# Y904A23-GF-DYGDSCH-V1_0.net
KiCad netlist of a schematic drawn in Altium Designer
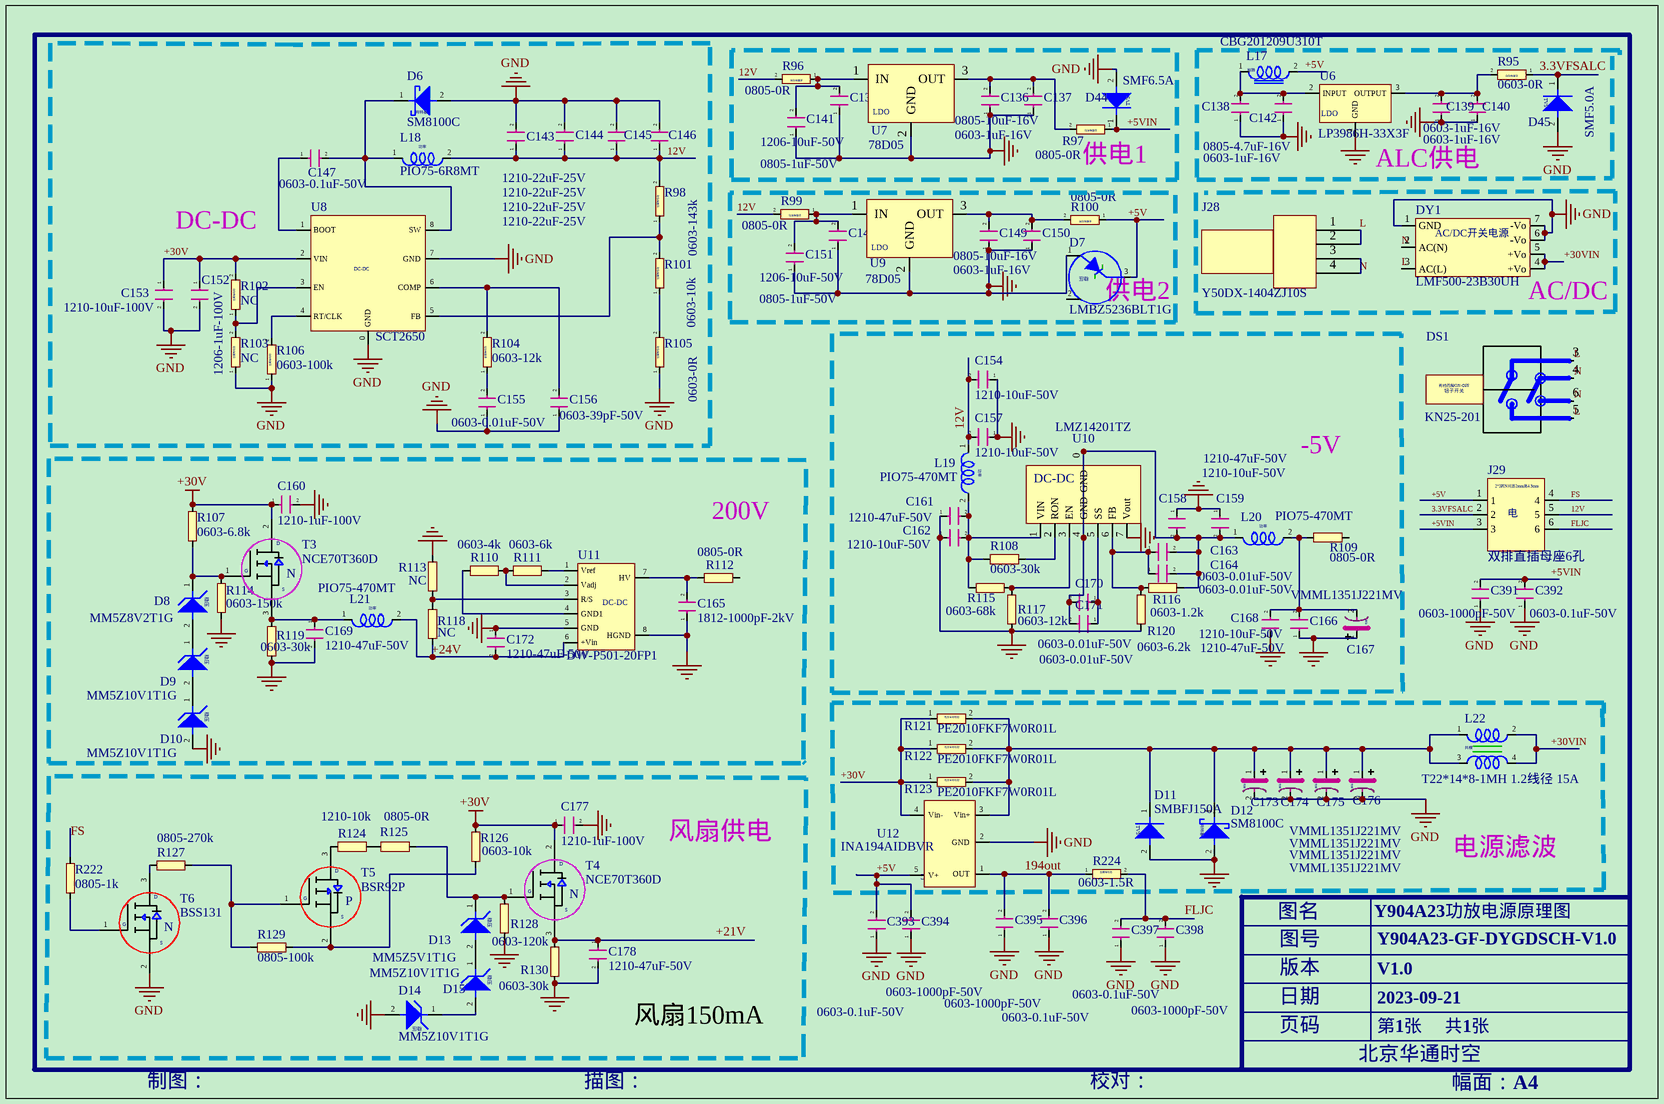
[diagram p0: Y904A23-GF-DYGDSCH-V1.0.SchDoc]

(export (version "E")
  (design (tool "Eeschema 10.0.6"))
  (components
    (comp (ref "C135")
      (value "0805-1uF-50V")
      (footprint "C0805")
      (description "陶瓷电容,厂家")
      (libsource (lib "电容") (part "Cap1"))
    )
    (comp (ref "C136")
      (value "0805-10uF-16V")
      (footprint "C0805")
      (description "陶瓷电容,厂家")
      (libsource (lib "电容") (part "Cap1"))
    )
    (comp (ref "C137")
      (value "0603-1uF-16V")
      (footprint "C0603")
      (description "陶瓷电容,厂家")
      (libsource (lib "电容") (part "Cap1"))
    )
    (comp (ref "C138")
      (value "0805-4.7uF-16V")
      (footprint "C0805")
      (description "陶瓷电容,厂家")
      (libsource (lib "电容") (part "Cap1"))
    )
    (comp (ref "C139")
      (value "0603-1uF-16V")
      (footprint "C0603")
      (description "陶瓷电容,厂家")
      (libsource (lib "电容") (part "Cap1"))
    )
    (comp (ref "C140")
      (value "0603-1uF-16V")
      (footprint "C0603")
      (description "陶瓷电容,厂家")
      (libsource (lib "电容") (part "Cap1"))
    )
    (comp (ref "C141")
      (value "1206-10uF-50V")
      (footprint "C1206")
      (description "陶瓷电容,厂家")
      (libsource (lib "电容") (part "Cap1"))
    )
    (comp (ref "C142")
      (value "0603-1uF-16V")
      (footprint "C0603")
      (description "陶瓷电容,厂家")
      (libsource (lib "电容") (part "Cap1"))
    )
    (comp (ref "C143")
      (value "1210-22uF-25V")
      (footprint "C1210")
      (description "陶瓷电容,厂家")
      (libsource (lib "电容") (part "Cap1"))
    )
    (comp (ref "C144")
      (value "1210-22uF-25V")
      (footprint "C1210")
      (description "陶瓷电容,厂家")
      (libsource (lib "电容") (part "Cap1"))
    )
    (comp (ref "C145")
      (value "1210-22uF-25V")
      (footprint "C1210")
      (description "陶瓷电容,厂家")
      (libsource (lib "电容") (part "Cap1"))
    )
    (comp (ref "C146")
      (value "1210-22uF-25V")
      (footprint "C1210")
      (description "陶瓷电容,厂家")
      (libsource (lib "电容") (part "Cap1"))
    )
    (comp (ref "C147")
      (value "0603-0.1uF-50V")
      (footprint "C0603")
      (description "陶瓷电容,厂家")
      (libsource (lib "电容") (part "Cap1"))
    )
    (comp (ref "C148")
      (value "0805-1uF-50V")
      (footprint "C0805")
      (description "陶瓷电容,厂家")
      (libsource (lib "电容") (part "Cap1"))
    )
    (comp (ref "C149")
      (value "0805-10uF-16V")
      (footprint "C0805")
      (description "陶瓷电容,厂家")
      (libsource (lib "电容") (part "Cap1"))
    )
    (comp (ref "C150")
      (value "0603-1uF-16V")
      (footprint "C0603")
      (description "陶瓷电容,厂家")
      (libsource (lib "电容") (part "Cap1"))
    )
    (comp (ref "C151")
      (value "1206-10uF-50V")
      (footprint "C1206")
      (description "陶瓷电容,厂家")
      (libsource (lib "电容") (part "Cap1"))
    )
    (comp (ref "C152")
      (value "1206-1uF-100V")
      (footprint "C1206")
      (description "陶瓷电容,厂家")
      (libsource (lib "电容") (part "Cap1"))
    )
    (comp (ref "C153")
      (value "1210-10uF-100V")
      (footprint "C1210")
      (description "陶瓷电容,厂家")
      (libsource (lib "电容") (part "Cap1"))
    )
    (comp (ref "C154")
      (value "1210-10uF-50V")
      (footprint "C1210")
      (description "陶瓷电容,厂家")
      (libsource (lib "电容") (part "Cap1"))
    )
    (comp (ref "C155")
      (value "0603-0.01uF-50V")
      (footprint "C0603")
      (description "陶瓷电容,厂家")
      (libsource (lib "电容") (part "Cap1"))
    )
    (comp (ref "C156")
      (value "0603-39pF-50V")
      (footprint "C0603")
      (description "陶瓷电容,厂家")
      (libsource (lib "电容") (part "Cap1"))
    )
    (comp (ref "C157")
      (value "1210-10uF-50V")
      (footprint "C1210")
      (description "陶瓷电容,厂家")
      (libsource (lib "电容") (part "Cap1"))
    )
    (comp (ref "C158")
      (value "1210-10uF-50V")
      (footprint "C1210")
      (description "陶瓷电容,厂家")
      (libsource (lib "电容") (part "Cap1"))
    )
    (comp (ref "C159")
      (value "1210-47uF-50V")
      (footprint "C1210")
      (description "陶瓷电容,厂家")
      (libsource (lib "电容") (part "Cap1"))
    )
    (comp (ref "C160")
      (value "1210-1uF-100V")
      (footprint "C1210")
      (description "陶瓷电容,厂家")
      (libsource (lib "电容") (part "Cap1"))
    )
    (comp (ref "C161")
      (value "1210-47uF-50V")
      (footprint "C1210")
      (description "陶瓷电容,厂家")
      (libsource (lib "电容") (part "Cap1"))
    )
    (comp (ref "C162")
      (value "1210-10uF-50V")
      (footprint "C1210")
      (description "陶瓷电容,厂家")
      (libsource (lib "电容") (part "Cap1"))
    )
    (comp (ref "C163")
      (value "0603-0.01uF-50V")
      (footprint "C0603")
      (description "陶瓷电容,厂家")
      (libsource (lib "电容") (part "Cap1"))
    )
    (comp (ref "C164")
      (value "0603-0.01uF-50V")
      (footprint "C0603")
      (description "陶瓷电容,厂家")
      (libsource (lib "电容") (part "Cap1"))
    )
    (comp (ref "C165")
      (value "1812-1000pF-2kV")
      (footprint "C1812")
      (description "陶瓷电容,厂家")
      (libsource (lib "电容") (part "Cap1"))
    )
    (comp (ref "C166")
      (value "1210-47uF-50V")
      (footprint "C1210")
      (description "陶瓷电容,厂家")
      (libsource (lib "电容") (part "Cap1"))
    )
    (comp (ref "C167")
      (value "VMML1351J221MV")
      (footprint "CAE-13.5X13.5X13.5mm(SMD)")
      (description "电解电容,Ymin永铭")
      (libsource (lib "电容") (part "VMML1351J221MV"))
    )
    (comp (ref "C168")
      (value "1210-10uF-50V")
      (footprint "C1210")
      (description "陶瓷电容,厂家")
      (libsource (lib "电容") (part "Cap1"))
    )
    (comp (ref "C169")
      (value "1210-47uF-50V")
      (footprint "C1210")
      (description "陶瓷电容,厂家")
      (libsource (lib "电容") (part "Cap1"))
    )
    (comp (ref "C170")
      (value "0603-0.01uF-50V")
      (footprint "C0603")
      (description "陶瓷电容,厂家")
      (libsource (lib "电容") (part "Cap1"))
    )
    (comp (ref "C171")
      (value "0603-0.01uF-50V")
      (footprint "C0603")
      (description "陶瓷电容,厂家")
      (libsource (lib "电容") (part "Cap1"))
    )
    (comp (ref "C172")
      (value "1210-47uF-50V")
      (footprint "C1210")
      (description "陶瓷电容,厂家")
      (libsource (lib "电容") (part "Cap1"))
    )
    (comp (ref "C173")
      (value "VMML1351J221MV")
      (footprint "CAE-13.5X13.5X13.5mm(SMD)")
      (description "电解电容,Ymin永铭")
      (libsource (lib "电容") (part "VMML1351J221MV"))
    )
    (comp (ref "C174")
      (value "VMML1351J221MV")
      (footprint "CAE-13.5X13.5X13.5mm(SMD)")
      (description "电解电容,Ymin永铭")
      (libsource (lib "电容") (part "VMML1351J221MV"))
    )
    (comp (ref "C175")
      (value "VMML1351J221MV")
      (footprint "CAE-13.5X13.5X13.5mm(SMD)")
      (description "电解电容,Ymin永铭")
      (libsource (lib "电容") (part "VMML1351J221MV"))
    )
    (comp (ref "C176")
      (value "VMML1351J221MV")
      (footprint "CAE-13.5X13.5X13.5mm(SMD)")
      (description "电解电容,Ymin永铭")
      (libsource (lib "电容") (part "VMML1351J221MV"))
    )
    (comp (ref "C177")
      (value "1210-1uF-100V")
      (footprint "C1210")
      (description "陶瓷电容,厂家")
      (libsource (lib "电容") (part "Cap1"))
    )
    (comp (ref "C178")
      (value "1210-47uF-50V")
      (footprint "C1210")
      (description "陶瓷电容,厂家")
      (libsource (lib "电容") (part "Cap1"))
    )
    (comp (ref "C391")
      (value "0603-1000pF-50V")
      (footprint "C0603")
      (description "陶瓷电容,厂家")
      (libsource (lib "电容") (part "Cap1"))
    )
    (comp (ref "C392")
      (value "0603-0.1uF-50V")
      (footprint "C0603")
      (description "陶瓷电容,厂家")
      (libsource (lib "电容") (part "Cap1"))
    )
    (comp (ref "C393")
      (value "0603-0.1uF-50V")
      (footprint "C0603")
      (description "陶瓷电容,厂家")
      (libsource (lib "电容") (part "Cap1"))
    )
    (comp (ref "C394")
      (value "0603-1000pF-50V")
      (footprint "C0603")
      (description "陶瓷电容,厂家")
      (libsource (lib "电容") (part "Cap1"))
    )
    (comp (ref "C395")
      (value "0603-1000pF-50V")
      (footprint "C0603")
      (description "陶瓷电容,厂家")
      (libsource (lib "电容") (part "Cap1"))
    )
    (comp (ref "C396")
      (value "0603-0.1uF-50V")
      (footprint "C0603")
      (description "陶瓷电容,厂家")
      (libsource (lib "电容") (part "Cap1"))
    )
    (comp (ref "C397")
      (value "0603-0.1uF-50V")
      (footprint "C0603")
      (description "陶瓷电容,厂家")
      (libsource (lib "电容") (part "Cap1"))
    )
    (comp (ref "C398")
      (value "0603-1000pF-50V")
      (footprint "C0603")
      (description "陶瓷电容,厂家")
      (libsource (lib "电容") (part "Cap1"))
    )
    (comp (ref "D6")
      (value "SM8100C")
      (footprint "SMC")
      (description "肖特基二极管,乐山无线电")
      (libsource (lib "二极管") (part "SM8100C"))
    )
    (comp (ref "D7")
      (value "LMBZ5236BLT1G")
      (footprint "SOT-23")
      (description "稳压二极管,乐山无线电")
      (libsource (lib "二极管") (part "LMBZ5236BLT1G"))
    )
    (comp (ref "D8")
      (value "MM5Z8V2T1G")
      (footprint "SOD-523")
      (description "稳压二极管,ON安森美")
      (libsource (lib "二极管") (part "MM5Z8V2T1G"))
    )
    (comp (ref "D9")
      (value "MM5Z10V1T1G")
      (footprint "SOD-523")
      (description "稳压二极管,ON安森美")
      (libsource (lib "二极管") (part "MM5Z10V1T1G"))
    )
    (comp (ref "D10")
      (value "MM5Z10V1T1G")
      (footprint "SOD-523")
      (description "稳压二极管,ON安森美")
      (libsource (lib "二极管") (part "MM5Z10V1T1G"))
    )
    (comp (ref "D11")
      (value "SMBFJ150A")
      (footprint "SMB")
      (description "TVS二极管,乐山无线电")
      (libsource (lib "二极管") (part "SMBFJ150A"))
    )
    (comp (ref "D12")
      (value "SM8100C")
      (footprint "SMC")
      (description "肖特基二极管,乐山无线电")
      (libsource (lib "二极管") (part "SM8100C"))
    )
    (comp (ref "D13")
      (value "MM5Z5V1T1G")
      (footprint "SOD-523")
      (description "稳压二极管,ON安森美")
      (libsource (lib "二极管") (part "MM5Z5V1T1G"))
    )
    (comp (ref "D14")
      (value "MM5Z10V1T1G")
      (footprint "SOD-523")
      (description "稳压二极管,ON安森美")
      (libsource (lib "二极管") (part "MM5Z10V1T1G"))
    )
    (comp (ref "D15")
      (value "MM5Z10V1T1G")
      (footprint "SOD-523")
      (description "稳压二极管,ON安森美")
      (libsource (lib "二极管") (part "MM5Z10V1T1G"))
    )
    (comp (ref "D44")
      (value "SMF6.5A")
      (footprint "SOD-123FL")
      (description "TVS二极管,江苏长电/长晶")
      (libsource (lib "二极管") (part "SMF6.5A"))
    )
    (comp (ref "D45")
      (value "SMF5.0A")
      (footprint "SOD-123FL")
      (description "TVS二极管,江苏长电/长晶")
      (libsource (lib "二极管") (part "SMF5.0A"))
    )
    (comp (ref "DS1")
      (value "KN25-201")
      (footprint "KN25-201")
      (description "钮子开关,上海星宇")
      (libsource (lib "待录入原理图库") (part "KN25-201"))
    )
    (comp (ref "DY1")
      (value "LMF500-23B30UH")
      (footprint "LMF500-23B30UH")
      (description "AC/DC 500W 机壳开关电源，广州金升阳")
      (libsource (lib "待录入原理图库") (part "LMF500-23B30UH"))
    )
    (comp (ref "J28")
      (value "Y50DX-1404ZJ10S")
      (footprint "Y50DX-1404ZJ10S")
      (description "航空插头座母,泰兴领航")
      (libsource (lib "待录入原理图库") (part "Y50DX-1404ZJ10S"))
    )
    (comp (ref "J29")
      (value "双排直插母座6孔")
      (footprint "双排直插母座6孔（2*3PIN间距2高4.3）")
      (description "电连接器,厂家")
      (libsource (lib "接插件") (part "双排直插母座6孔"))
    )
    (comp (ref "L17")
      (value "CBG201209U310T")
      (footprint "L0805")
      (description "磁珠,风华")
      (libsource (lib "电感") (part "CBG201209U310T"))
    )
    (comp (ref "L18")
      (value "PIO75-6R8MT")
      (footprint "L7.8x7.0x5.0")
      (description "功率电感,风华")
      (libsource (lib "电感") (part "PIO75-6R8MT"))
    )
    (comp (ref "L19")
      (value "PIO75-470MT")
      (footprint "L7.8x7.0x5.0")
      (description "功率电感,风华")
      (libsource (lib "电感") (part "PIO75-470MT"))
    )
    (comp (ref "L20")
      (value "PIO75-470MT")
      (footprint "L7.8x7.0x5.0")
      (description "功率电感,风华")
      (libsource (lib "电感") (part "PIO75-470MT"))
    )
    (comp (ref "L21")
      (value "PIO75-470MT")
      (footprint "L7.8x7.0x5.0")
      (description "功率电感,风华")
      (libsource (lib "电感") (part "PIO75-470MT"))
    )
    (comp (ref "L22")
      (value "T22*14*8-1MH 1.2线径 15A")
      (footprint "T22*14*8")
      (description "共模电感,深圳凯必达")
      (libsource (lib "待录入原理图库") (part "T22*14*8-1MH 1.2线径 15A"))
    )
    (comp (ref "R95")
      (value "0603-0R")
      (footprint "R0603")
      (description "金属釉电阻,厂家")
      (libsource (lib "电阻") (part "Resistance"))
    )
    (comp (ref "R96")
      (value "0805-0R")
      (footprint "R0805")
      (description "金属釉电阻,厂家")
      (libsource (lib "电阻") (part "Resistance"))
    )
    (comp (ref "R97")
      (value "0805-0R")
      (footprint "R0805")
      (description "金属釉电阻,厂家")
      (libsource (lib "电阻") (part "Resistance"))
    )
    (comp (ref "R98")
      (value "0603-143k")
      (footprint "R0603")
      (description "金属釉电阻,厂家")
      (libsource (lib "") (part "Resistance_5"))
    )
    (comp (ref "R99")
      (value "0805-0R")
      (footprint "R0805")
      (description "金属釉电阻,厂家")
      (libsource (lib "电阻") (part "Resistance"))
    )
    (comp (ref "R100")
      (value "0805-0R")
      (footprint "R0805")
      (description "金属釉电阻,厂家")
      (libsource (lib "电阻") (part "Resistance"))
    )
    (comp (ref "R101")
      (value "0603-10k")
      (footprint "R0603")
      (description "金属釉电阻,厂家")
      (libsource (lib "") (part "Resistance_5"))
    )
    (comp (ref "R102")
      (value "NC")
      (footprint "R0603")
      (description "金属釉电阻,厂家")
      (libsource (lib "") (part "Resistance_5"))
    )
    (comp (ref "R103")
      (value "NC")
      (footprint "R0603")
      (description "金属釉电阻,厂家")
      (libsource (lib "") (part "Resistance_5"))
    )
    (comp (ref "R104")
      (value "0603-12k")
      (footprint "R0603")
      (description "金属釉电阻,厂家")
      (libsource (lib "") (part "Resistance_5"))
    )
    (comp (ref "R105")
      (value "0603-0R")
      (footprint "R0603")
      (description "金属釉电阻,厂家")
      (libsource (lib "") (part "Resistance_5"))
    )
    (comp (ref "R106")
      (value "0603-100k")
      (footprint "R0603")
      (description "金属釉电阻,厂家")
      (libsource (lib "") (part "Resistance_5"))
    )
    (comp (ref "R107")
      (value "0603-6.8k")
      (footprint "R0603")
      (description "金属釉电阻,厂家")
      (libsource (lib "") (part "Resistance_2"))
    )
    (comp (ref "R108")
      (value "0603-30k")
      (footprint "R0603")
      (description "金属釉电阻,厂家")
      (libsource (lib "") (part "Resistance_4"))
    )
    (comp (ref "R109")
      (value "0805-0R")
      (footprint "R0805")
      (description "金属釉电阻,厂家")
      (libsource (lib "") (part "Resistance_2"))
    )
    (comp (ref "R110")
      (value "0603-4k")
      (footprint "R0603")
      (description "金属釉电阻,厂家")
      (libsource (lib "") (part "Resistance_1"))
    )
    (comp (ref "R111")
      (value "0603-6k")
      (footprint "R0603")
      (description "金属釉电阻,厂家")
      (libsource (lib "") (part "Resistance_1"))
    )
    (comp (ref "R112")
      (value "0805-0R")
      (footprint "R0805")
      (description "金属釉电阻,厂家")
      (libsource (lib "") (part "Resistance_4"))
    )
    (comp (ref "R113")
      (value "NC")
      (footprint "R0603")
      (description "金属釉电阻,厂家")
      (libsource (lib "") (part "Resistance_4"))
    )
    (comp (ref "R114")
      (value "0603-150k")
      (footprint "R0603")
      (description "金属釉电阻,厂家")
      (libsource (lib "") (part "Resistance_2"))
    )
    (comp (ref "R115")
      (value "0603-68k")
      (footprint "R0603")
      (description "金属釉电阻,厂家")
      (libsource (lib "") (part "Resistance_3"))
    )
    (comp (ref "R116")
      (value "0603-1.2k")
      (footprint "R0603")
      (description "金属釉电阻,厂家")
      (libsource (lib "") (part "Resistance_2"))
    )
    (comp (ref "R117")
      (value "0603-12k")
      (footprint "R0603")
      (description "金属釉电阻,厂家")
      (libsource (lib "") (part "Resistance_1"))
    )
    (comp (ref "R118")
      (value "NC")
      (footprint "R0603")
      (description "金属釉电阻,厂家")
      (libsource (lib "") (part "Resistance_3"))
    )
    (comp (ref "R119")
      (value "0603-30k")
      (footprint "R0603")
      (description "金属釉电阻,厂家")
      (libsource (lib "") (part "Resistance_2"))
    )
    (comp (ref "R120")
      (value "0603-6.2k")
      (footprint "R0603")
      (description "金属釉电阻,厂家")
      (libsource (lib "") (part "Resistance_3"))
    )
    (comp (ref "R121")
      (value "PE2010FKF7W0R01L")
      (footprint "R2010")
      (description "电流采样电阻,YAGEO(国巨)")
      (libsource (lib "待录入原理图库") (part "PE2010FKF7W0R01L"))
    )
    (comp (ref "R122")
      (value "PE2010FKF7W0R01L")
      (footprint "R2010")
      (description "电流采样电阻,YAGEO(国巨)")
      (libsource (lib "待录入原理图库") (part "PE2010FKF7W0R01L"))
    )
    (comp (ref "R123")
      (value "PE2010FKF7W0R01L")
      (footprint "R2010")
      (description "电流采样电阻,YAGEO(国巨)")
      (libsource (lib "待录入原理图库") (part "PE2010FKF7W0R01L"))
    )
    (comp (ref "R124")
      (value "1210-10k")
      (footprint "R1210")
      (description "金属釉电阻,厂家")
      (libsource (lib "") (part "Resistance_3"))
    )
    (comp (ref "R125")
      (value "0805-0R")
      (footprint "R0805")
      (description "金属釉电阻,厂家")
      (libsource (lib "") (part "Resistance_4"))
    )
    (comp (ref "R126")
      (value "0603-10k")
      (footprint "R0603")
      (description "金属釉电阻,厂家")
      (libsource (lib "") (part "Resistance_2"))
    )
    (comp (ref "R127")
      (value "0805-270k")
      (footprint "R0805")
      (description "金属釉电阻,厂家")
      (libsource (lib "") (part "Resistance_3"))
    )
    (comp (ref "R128")
      (value "0603-120k")
      (footprint "R0603")
      (description "金属釉电阻,厂家")
      (libsource (lib "") (part "Resistance_2"))
    )
    (comp (ref "R129")
      (value "0805-100k")
      (footprint "R0805")
      (description "金属釉电阻,厂家")
      (libsource (lib "") (part "Resistance_3"))
    )
    (comp (ref "R130")
      (value "0603-30k")
      (footprint "R0603")
      (description "金属釉电阻,厂家")
      (libsource (lib "") (part "Resistance_2"))
    )
    (comp (ref "R222")
      (value "0805-1k")
      (footprint "R0805")
      (description "金属釉电阻,厂家")
      (libsource (lib "") (part "Resistance_1"))
    )
    (comp (ref "R224")
      (value "0603-1.5R")
      (footprint "R0603")
      (description "金属釉电阻,厂家")
      (libsource (lib "") (part "Resistance_6"))
    )
    (comp (ref "T3")
      (value "NCE70T360D")
      (footprint "TO-263-2")
      (description "NMOS,无锡新洁能")
      (libsource (lib "MOS管") (part "NCE70T360D"))
    )
    (comp (ref "T4")
      (value "NCE70T360D")
      (footprint "TO-263-2")
      (description "NMOS,无锡新洁能")
      (libsource (lib "MOS管") (part "NCE70T360D"))
    )
    (comp (ref "T5")
      (value "BSR92P")
      (footprint "SOT-23")
      (description "PMOS,Infineon英飞凌")
      (libsource (lib "MOS管") (part "BSR92P"))
    )
    (comp (ref "T6")
      (value "BSS131")
      (footprint "SOT-23")
      (description "NMOS,Infineon英飞凌")
      (libsource (lib "MOS管") (part "BSS131"))
    )
    (comp (ref "U6")
      (value "LP3986H-33X3F")
      (footprint "SOT-89")
      (description "LDO,微源半导体")
      (libsource (lib "电源类") (part "LP3986H-33X3F"))
    )
    (comp (ref "U7")
      (value "78D05")
      (footprint "TO-252")
      (description "LDO,佛山蓝箭")
      (libsource (lib "电源类") (part "78D05"))
    )
    (comp (ref "U8")
      (value "SCT2650")
      (footprint "ESOP8L")
      (description "DC-DC,芯洲科技")
      (libsource (lib "电源类") (part "SCT2650"))
    )
    (comp (ref "U9")
      (value "78D05")
      (footprint "TO-252")
      (description "LDO,佛山蓝箭")
      (libsource (lib "电源类") (part "78D05"))
    )
    (comp (ref "U10")
      (value "LMZ14201TZ")
      (footprint "TO-263-7")
      (description "DC-DC,TI德州仪器")
      (libsource (lib "电源类") (part "LMZ14201TZ"))
    )
    (comp (ref "U11")
      (value "DW-P501-20FP1")
      (footprint "DW-PXXX-20XP1")
      (description "DC-DC,东文")
      (libsource (lib "电源类") (part "DW-P501-20FP1"))
    )
    (comp (ref "U12")
      (value "INA194AIDBVR")
      (footprint "SOT-23-5")
      (description "分流监测计,TI")
      (libsource (lib "待录入原理图库") (part "INA194AIDBVR"))
    )
  )
  (nets
    (net (code "1") (name "+30V") (class "Default")
      (node (ref "C152") (pin "1") (pinfunction "1_1") (pintype "passive"))
      (node (ref "C153") (pin "1") (pinfunction "1_1") (pintype "passive"))
      (node (ref "C160") (pin "1") (pinfunction "1_1") (pintype "passive"))
      (node (ref "C177") (pin "1") (pinfunction "1_1") (pintype "passive"))
      (node (ref "R102") (pin "2") (pinfunction "2_2") (pintype "passive"))
      (node (ref "R107") (pin "1") (pinfunction "1_1") (pintype "passive"))
      (node (ref "R121") (pin "1") (pinfunction "1_1") (pintype "passive"))
      (node (ref "R122") (pin "1") (pinfunction "1_1") (pintype "passive"))
      (node (ref "R123") (pin "1") (pinfunction "1_1") (pintype "passive"))
      (node (ref "R126") (pin "1") (pinfunction "1_1") (pintype "passive"))
      (node (ref "T3") (pin "2") (pinfunction "D_2") (pintype "passive"))
      (node (ref "T4") (pin "2") (pinfunction "D_2") (pintype "passive"))
      (node (ref "U12") (pin "4") (pinfunction "Vin-_4") (pintype "passive"))
      (node (ref "U8") (pin "2") (pinfunction "VIN_2") (pintype "passive"))
    )
    (net (code "2") (name "/+5V") (class "Default")
      (node (ref "C393") (pin "2") (pinfunction "2_2") (pintype "passive"))
      (node (ref "C394") (pin "2") (pinfunction "2_2") (pintype "passive"))
      (node (ref "D7") (pin "3") (pinfunction "3_3") (pintype "passive"))
      (node (ref "J29") (pin "1") (pinfunction "1_1") (pintype "passive"))
      (node (ref "L17") (pin "2") (pinfunction "2_2") (pintype "passive"))
      (node (ref "R100") (pin "1") (pinfunction "1_1") (pintype "passive"))
      (node (ref "U12") (pin "5") (pinfunction "V+_5") (pintype "passive"))
    )
    (net (code "3") (name "/+5VIN") (class "Default")
      (node (ref "C391") (pin "2") (pinfunction "2_2") (pintype "passive"))
      (node (ref "C392") (pin "2") (pinfunction "2_2") (pintype "passive"))
      (node (ref "D44") (pin "1") (pinfunction "1_1") (pintype "passive"))
      (node (ref "J29") (pin "3") (pinfunction "3_3") (pintype "passive"))
      (node (ref "R97") (pin "1") (pinfunction "1_1") (pintype "passive"))
    )
    (net (code "4") (name "/+21V") (class "Default")
      (node (ref "C178") (pin "1") (pinfunction "1_1") (pintype "passive"))
      (node (ref "R130") (pin "1") (pinfunction "1_1") (pintype "passive"))
      (node (ref "T4") (pin "3") (pinfunction "S_3") (pintype "passive"))
    )
    (net (code "6") (name "/+30VIN") (class "Default")
      (node (ref "DY1") (pin "4") (pinfunction "+Vo_4") (pintype "passive"))
      (node (ref "DY1") (pin "5") (pinfunction "+Vo_5") (pintype "passive"))
      (node (ref "L22") (pin "2") (pinfunction "2_2") (pintype "passive"))
      (node (ref "L22") (pin "4") (pinfunction "4_4") (pintype "passive"))
    )
    (net (code "7") (name "/3.3VFSALC") (class "Default")
      (node (ref "D45") (pin "1") (pinfunction "1_1") (pintype "passive"))
      (node (ref "J29") (pin "2") (pinfunction "2_2") (pintype "passive"))
      (node (ref "R95") (pin "1") (pinfunction "1_1") (pintype "passive"))
    )
    (net (code "8") (name "/12V") (class "Default")
      (node (ref "C143") (pin "1") (pinfunction "1_1") (pintype "passive"))
      (node (ref "C144") (pin "1") (pinfunction "1_1") (pintype "passive"))
      (node (ref "C145") (pin "1") (pinfunction "1_1") (pintype "passive"))
      (node (ref "C146") (pin "1") (pinfunction "1_1") (pintype "passive"))
      (node (ref "C154") (pin "2") (pinfunction "2_2") (pintype "passive"))
      (node (ref "C157") (pin "2") (pinfunction "2_2") (pintype "passive"))
      (node (ref "J29") (pin "5") (pinfunction "5_5") (pintype "passive"))
      (node (ref "L18") (pin "2") (pinfunction "2_2") (pintype "passive"))
      (node (ref "L19") (pin "1") (pinfunction "1_1") (pintype "passive"))
      (node (ref "R96") (pin "2") (pinfunction "2_2") (pintype "passive"))
      (node (ref "R98") (pin "2") (pinfunction "2_2") (pintype "passive"))
      (node (ref "R99") (pin "2") (pinfunction "2_2") (pintype "passive"))
    )
    (net (code "9") (name "/194out") (class "Default")
      (node (ref "C395") (pin "2") (pinfunction "2_2") (pintype "passive"))
      (node (ref "C396") (pin "2") (pinfunction "2_2") (pintype "passive"))
      (node (ref "R224") (pin "1") (pinfunction "1_1") (pintype "passive"))
      (node (ref "U12") (pin "1") (pinfunction "OUT_1") (pintype "passive"))
    )
    (net (code "10") (name "/FLJC") (class "Default")
      (node (ref "C397") (pin "2") (pinfunction "2_2") (pintype "passive"))
      (node (ref "C398") (pin "2") (pinfunction "2_2") (pintype "passive"))
      (node (ref "J29") (pin "6") (pinfunction "6_6") (pintype "passive"))
      (node (ref "R224") (pin "2") (pinfunction "2_2") (pintype "passive"))
    )
    (net (code "11") (name "/FS") (class "Default")
      (node (ref "J29") (pin "4") (pinfunction "4_4") (pintype "passive"))
      (node (ref "R222") (pin "2") (pinfunction "2_2") (pintype "passive"))
    )
    (net (code "12") (name "/L") (class "Default")
      (node (ref "DS1") (pin "3") (pintype "passive"))
      (node (ref "DS1") (pin "5") (pintype "passive"))
      (node (ref "DY1") (pin "3") (pinfunction "AC(L)_3") (pintype "passive"))
      (node (ref "J28") (pin "1") (pintype "passive"))
      (node (ref "J28") (pin "2") (pintype "passive"))
    )
    (net (code "13") (name "/N") (class "Default")
      (node (ref "DS1") (pin "4") (pintype "passive"))
      (node (ref "DS1") (pin "6") (pintype "passive"))
      (node (ref "DY1") (pin "2") (pinfunction "AC(N)_2") (pintype "passive"))
      (node (ref "J28") (pin "3") (pintype "passive"))
      (node (ref "J28") (pin "4") (pintype "passive"))
    )
    (net (code "14") (name "GND") (class "Default")
      (node (ref "C135") (pin "1") (pinfunction "1_1") (pintype "passive"))
      (node (ref "C136") (pin "1") (pinfunction "1_1") (pintype "passive"))
      (node (ref "C137") (pin "1") (pinfunction "1_1") (pintype "passive"))
      (node (ref "C138") (pin "1") (pinfunction "1_1") (pintype "passive"))
      (node (ref "C139") (pin "1") (pinfunction "1_1") (pintype "passive"))
      (node (ref "C140") (pin "1") (pinfunction "1_1") (pintype "passive"))
      (node (ref "C141") (pin "1") (pinfunction "1_1") (pintype "passive"))
      (node (ref "C142") (pin "1") (pinfunction "1_1") (pintype "passive"))
      (node (ref "C143") (pin "2") (pinfunction "2_2") (pintype "passive"))
      (node (ref "C144") (pin "2") (pinfunction "2_2") (pintype "passive"))
      (node (ref "C145") (pin "2") (pinfunction "2_2") (pintype "passive"))
      (node (ref "C146") (pin "2") (pinfunction "2_2") (pintype "passive"))
      (node (ref "C148") (pin "1") (pinfunction "1_1") (pintype "passive"))
      (node (ref "C149") (pin "1") (pinfunction "1_1") (pintype "passive"))
      (node (ref "C150") (pin "1") (pinfunction "1_1") (pintype "passive"))
      (node (ref "C151") (pin "1") (pinfunction "1_1") (pintype "passive"))
      (node (ref "C152") (pin "2") (pinfunction "2_2") (pintype "passive"))
      (node (ref "C153") (pin "2") (pinfunction "2_2") (pintype "passive"))
      (node (ref "C154") (pin "1") (pinfunction "1_1") (pintype "passive"))
      (node (ref "C155") (pin "1") (pinfunction "1_1") (pintype "passive"))
      (node (ref "C156") (pin "1") (pinfunction "1_1") (pintype "passive"))
      (node (ref "C157") (pin "1") (pinfunction "1_1") (pintype "passive"))
      (node (ref "C158") (pin "1") (pinfunction "1_1") (pintype "passive"))
      (node (ref "C159") (pin "1") (pinfunction "1_1") (pintype "passive"))
      (node (ref "C160") (pin "2") (pinfunction "2_2") (pintype "passive"))
      (node (ref "C161") (pin "1") (pinfunction "1_1") (pintype "passive"))
      (node (ref "C162") (pin "1") (pinfunction "1_1") (pintype "passive"))
      (node (ref "C165") (pin "1") (pinfunction "1_1") (pintype "passive"))
      (node (ref "C166") (pin "1") (pinfunction "1_1") (pintype "passive"))
      (node (ref "C167") (pin "1") (pinfunction "1_1") (pintype "passive"))
      (node (ref "C168") (pin "1") (pinfunction "1_1") (pintype "passive"))
      (node (ref "C169") (pin "2") (pinfunction "2_2") (pintype "passive"))
      (node (ref "C172") (pin "1") (pinfunction "1_1") (pintype "passive"))
      (node (ref "C173") (pin "2") (pinfunction "2_2") (pintype "passive"))
      (node (ref "C174") (pin "2") (pinfunction "2_2") (pintype "passive"))
      (node (ref "C175") (pin "2") (pinfunction "2_2") (pintype "passive"))
      (node (ref "C176") (pin "2") (pinfunction "2_2") (pintype "passive"))
      (node (ref "C177") (pin "2") (pinfunction "2_2") (pintype "passive"))
      (node (ref "C178") (pin "2") (pinfunction "2_2") (pintype "passive"))
      (node (ref "C391") (pin "1") (pinfunction "1_1") (pintype "passive"))
      (node (ref "C392") (pin "1") (pinfunction "1_1") (pintype "passive"))
      (node (ref "C393") (pin "1") (pinfunction "1_1") (pintype "passive"))
      (node (ref "C394") (pin "1") (pinfunction "1_1") (pintype "passive"))
      (node (ref "C395") (pin "1") (pinfunction "1_1") (pintype "passive"))
      (node (ref "C396") (pin "1") (pinfunction "1_1") (pintype "passive"))
      (node (ref "C397") (pin "1") (pinfunction "1_1") (pintype "passive"))
      (node (ref "C398") (pin "1") (pinfunction "1_1") (pintype "passive"))
      (node (ref "D10") (pin "2") (pinfunction "2_2") (pintype "passive"))
      (node (ref "D11") (pin "2") (pinfunction "2_2") (pintype "passive"))
      (node (ref "D12") (pin "2") (pinfunction "2_2") (pintype "passive"))
      (node (ref "D14") (pin "2") (pinfunction "2_2") (pintype "passive"))
      (node (ref "D44") (pin "2") (pinfunction "2_2") (pintype "passive"))
      (node (ref "D45") (pin "2") (pinfunction "2_2") (pintype "passive"))
      (node (ref "D6") (pin "2") (pinfunction "2_2") (pintype "passive"))
      (node (ref "D7") (pin "1") (pinfunction "1_1") (pintype "passive"))
      (node (ref "DY1") (pin "1") (pinfunction "GND_1") (pintype "passive"))
      (node (ref "DY1") (pin "6") (pinfunction "-Vo_6") (pintype "passive"))
      (node (ref "DY1") (pin "7") (pinfunction "-Vo_7") (pintype "passive"))
      (node (ref "R103") (pin "1") (pinfunction "1_1") (pintype "passive"))
      (node (ref "R105") (pin "1") (pinfunction "1_1") (pintype "passive"))
      (node (ref "R106") (pin "1") (pinfunction "1_1") (pintype "passive"))
      (node (ref "R113") (pin "1") (pinfunction "1_1") (pintype "passive"))
      (node (ref "R114") (pin "2") (pinfunction "2_2") (pintype "passive"))
      (node (ref "R117") (pin "1") (pinfunction "1_1") (pintype "passive"))
      (node (ref "R119") (pin "2") (pinfunction "2_2") (pintype "passive"))
      (node (ref "R120") (pin "1") (pinfunction "1_1") (pintype "passive"))
      (node (ref "R128") (pin "2") (pinfunction "2_2") (pintype "passive"))
      (node (ref "R130") (pin "2") (pinfunction "2_2") (pintype "passive"))
      (node (ref "T6") (pin "2") (pinfunction "S_2") (pintype "passive"))
      (node (ref "U10") (pin "7") (pinfunction "Vout_7") (pintype "passive"))
      (node (ref "U11") (pin "5") (pinfunction "GND_5") (pintype "passive"))
      (node (ref "U11") (pin "8") (pinfunction "HGND_8") (pintype "passive"))
      (node (ref "U12") (pin "2") (pinfunction "GND_2") (pintype "passive"))
      (node (ref "U6") (pin "1") (pinfunction "GND_1") (pintype "passive"))
      (node (ref "U7") (pin "2") (pinfunction "GND_2") (pintype "passive"))
      (node (ref "U8") (pin "0") (pinfunction "GND_0") (pintype "passive"))
      (node (ref "U8") (pin "7") (pinfunction "GND_7") (pintype "passive"))
      (node (ref "U9") (pin "2") (pinfunction "GND_2") (pintype "passive"))
    )
    (net (code "15") (name "Net-(C155-Pad2)") (class "Default")
      (node (ref "C155") (pin "2") (pinfunction "2_2") (pintype "passive"))
      (node (ref "R104") (pin "1") (pinfunction "1_1") (pintype "passive"))
    )
    (net (code "16") (name "Net-(C158-Pad2)") (class "Default")
      (node (ref "C158") (pin "2") (pinfunction "2_2") (pintype "passive"))
      (node (ref "C159") (pin "2") (pinfunction "2_2") (pintype "passive"))
      (node (ref "C163") (pin "2") (pinfunction "2_2") (pintype "passive"))
      (node (ref "C164") (pin "2") (pinfunction "2_2") (pintype "passive"))
      (node (ref "C170") (pin "2") (pinfunction "2_2") (pintype "passive"))
      (node (ref "C171") (pin "2") (pinfunction "2_2") (pintype "passive"))
      (node (ref "L20") (pin "1") (pinfunction "1_1") (pintype "passive"))
      (node (ref "R116") (pin "1") (pinfunction "1_1") (pintype "passive"))
      (node (ref "U10") (pin "0") (pinfunction "GND_0") (pintype "passive"))
      (node (ref "U10") (pin "4") (pinfunction "GND_4") (pintype "passive"))
    )
    (net (code "17") (name "Net-(C166-Pad2)") (class "Default")
      (node (ref "C166") (pin "2") (pinfunction "2_2") (pintype "passive"))
      (node (ref "C167") (pin "2") (pinfunction "2_2") (pintype "passive"))
      (node (ref "C168") (pin "2") (pinfunction "2_2") (pintype "passive"))
      (node (ref "L20") (pin "2") (pinfunction "2_2") (pintype "passive"))
      (node (ref "R109") (pin "2") (pinfunction "2_2") (pintype "passive"))
    )
    (net (code "18") (name "Net-(D8-Pad2)") (class "Default")
      (node (ref "D8") (pin "2") (pinfunction "2_2") (pintype "passive"))
      (node (ref "D9") (pin "1") (pinfunction "1_1") (pintype "passive"))
    )
    (net (code "19") (name "Net-(D10-Pad1)") (class "Default")
      (node (ref "D10") (pin "1") (pinfunction "1_1") (pintype "passive"))
      (node (ref "D9") (pin "2") (pinfunction "2_2") (pintype "passive"))
    )
    (net (code "20") (name "Net-(D13-Pad2)") (class "Default")
      (node (ref "D13") (pin "2") (pinfunction "2_2") (pintype "passive"))
      (node (ref "D15") (pin "1") (pinfunction "1_1") (pintype "passive"))
    )
    (net (code "21") (name "Net-(D14-Pad1)") (class "Default")
      (node (ref "D14") (pin "1") (pinfunction "1_1") (pintype "passive"))
      (node (ref "D15") (pin "2") (pinfunction "2_2") (pintype "passive"))
    )
    (net (code "22") (name "Net-(R101-Pad1)") (class "Default")
      (node (ref "R101") (pin "1") (pinfunction "1_1") (pintype "passive"))
      (node (ref "R105") (pin "2") (pinfunction "2_2") (pintype "passive"))
    )
    (net (code "23") (name "Net-(R124-Pad2)") (class "Default")
      (node (ref "R124") (pin "2") (pinfunction "2_2") (pintype "passive"))
      (node (ref "R125") (pin "2") (pinfunction "2_2") (pintype "passive"))
    )
    (net (code "24") (name "Net-(T3-G)") (class "Default")
      (node (ref "D8") (pin "1") (pinfunction "1_1") (pintype "passive"))
      (node (ref "R107") (pin "2") (pinfunction "2_2") (pintype "passive"))
      (node (ref "R114") (pin "1") (pinfunction "1_1") (pintype "passive"))
      (node (ref "T3") (pin "1") (pinfunction "G_1") (pintype "passive"))
    )
    (net (code "25") (name "Net-(T3-S)") (class "Default")
      (node (ref "C169") (pin "1") (pinfunction "1_1") (pintype "passive"))
      (node (ref "L21") (pin "1") (pinfunction "1_1") (pintype "passive"))
      (node (ref "R119") (pin "1") (pinfunction "1_1") (pintype "passive"))
      (node (ref "T3") (pin "3") (pinfunction "S_3") (pintype "passive"))
    )
    (net (code "26") (name "Net-(T4-G)") (class "Default")
      (node (ref "D13") (pin "1") (pinfunction "1_1") (pintype "passive"))
      (node (ref "R125") (pin "1") (pinfunction "1_1") (pintype "passive"))
      (node (ref "R128") (pin "1") (pinfunction "1_1") (pintype "passive"))
      (node (ref "T4") (pin "1") (pinfunction "G_1") (pintype "passive"))
    )
    (net (code "27") (name "Net-(T5-D)") (class "Default")
      (node (ref "R124") (pin "1") (pinfunction "1_1") (pintype "passive"))
      (node (ref "T5") (pin "3") (pinfunction "D_3") (pintype "passive"))
    )
    (net (code "28") (name "Net-(T5-G)") (class "Default")
      (node (ref "R127") (pin "2") (pinfunction "2_2") (pintype "passive"))
      (node (ref "R129") (pin "1") (pinfunction "1_1") (pintype "passive"))
      (node (ref "T5") (pin "1") (pinfunction "G_1") (pintype "passive"))
    )
    (net (code "29") (name "Net-(T5-S)") (class "Default")
      (node (ref "R126") (pin "2") (pinfunction "2_2") (pintype "passive"))
      (node (ref "R129") (pin "2") (pinfunction "2_2") (pintype "passive"))
      (node (ref "T5") (pin "2") (pinfunction "S_2") (pintype "passive"))
    )
    (net (code "30") (name "Net-(T6-D)") (class "Default")
      (node (ref "R127") (pin "1") (pinfunction "1_1") (pintype "passive"))
      (node (ref "T6") (pin "3") (pinfunction "D_3") (pintype "passive"))
    )
    (net (code "31") (name "Net-(T6-G)") (class "Default")
      (node (ref "R222") (pin "1") (pinfunction "1_1") (pintype "passive"))
      (node (ref "T6") (pin "1") (pinfunction "G_1") (pintype "passive"))
    )
    (net (code "32") (name "Net-(U6-INPUT)") (class "Default")
      (node (ref "C138") (pin "2") (pinfunction "2_2") (pintype "passive"))
      (node (ref "C142") (pin "2") (pinfunction "2_2") (pintype "passive"))
      (node (ref "L17") (pin "1") (pinfunction "1_1") (pintype "passive"))
      (node (ref "U6") (pin "2") (pinfunction "INPUT_2") (pintype "passive"))
    )
    (net (code "33") (name "Net-(U6-OUTPUT)") (class "Default")
      (node (ref "C139") (pin "2") (pinfunction "2_2") (pintype "passive"))
      (node (ref "C140") (pin "2") (pinfunction "2_2") (pintype "passive"))
      (node (ref "R95") (pin "2") (pinfunction "2_2") (pintype "passive"))
      (node (ref "U6") (pin "3") (pinfunction "OUTPUT_3") (pintype "passive"))
    )
    (net (code "34") (name "Net-(U7-IN)") (class "Default")
      (node (ref "C135") (pin "2") (pinfunction "2_2") (pintype "passive"))
      (node (ref "C141") (pin "2") (pinfunction "2_2") (pintype "passive"))
      (node (ref "R96") (pin "1") (pinfunction "1_1") (pintype "passive"))
      (node (ref "U7") (pin "1") (pinfunction "IN_1") (pintype "passive"))
    )
    (net (code "35") (name "Net-(U7-OUT)") (class "Default")
      (node (ref "C136") (pin "2") (pinfunction "2_2") (pintype "passive"))
      (node (ref "C137") (pin "2") (pinfunction "2_2") (pintype "passive"))
      (node (ref "R97") (pin "2") (pinfunction "2_2") (pintype "passive"))
      (node (ref "U7") (pin "3") (pinfunction "OUT_3") (pintype "passive"))
    )
    (net (code "36") (name "Net-(U8-BOOT)") (class "Default")
      (node (ref "C147") (pin "1") (pinfunction "1_1") (pintype "passive"))
      (node (ref "U8") (pin "1") (pinfunction "BOOT_1") (pintype "passive"))
    )
    (net (code "37") (name "Net-(U8-COMP)") (class "Default")
      (node (ref "C156") (pin "2") (pinfunction "2_2") (pintype "passive"))
      (node (ref "R104") (pin "2") (pinfunction "2_2") (pintype "passive"))
      (node (ref "U8") (pin "6") (pinfunction "COMP_6") (pintype "passive"))
    )
    (net (code "38") (name "Net-(U8-EN)") (class "Default")
      (node (ref "R102") (pin "1") (pinfunction "1_1") (pintype "passive"))
      (node (ref "R103") (pin "2") (pinfunction "2_2") (pintype "passive"))
      (node (ref "U8") (pin "3") (pinfunction "EN_3") (pintype "passive"))
    )
    (net (code "39") (name "Net-(U8-FB)") (class "Default")
      (node (ref "R101") (pin "2") (pinfunction "2_2") (pintype "passive"))
      (node (ref "R98") (pin "1") (pinfunction "1_1") (pintype "passive"))
      (node (ref "U8") (pin "5") (pinfunction "FB_5") (pintype "passive"))
    )
    (net (code "40") (name "Net-(U8-RT{slash}CLK)") (class "Default")
      (node (ref "R106") (pin "2") (pinfunction "2_2") (pintype "passive"))
      (node (ref "U8") (pin "4") (pinfunction "RT/CLK_4") (pintype "passive"))
    )
    (net (code "41") (name "Net-(U8-SW)") (class "Default")
      (node (ref "C147") (pin "2") (pinfunction "2_2") (pintype "passive"))
      (node (ref "D6") (pin "1") (pinfunction "1_1") (pintype "passive"))
      (node (ref "L18") (pin "1") (pinfunction "1_1") (pintype "passive"))
      (node (ref "U8") (pin "8") (pinfunction "SW_8") (pintype "passive"))
    )
    (net (code "42") (name "Net-(U9-IN)") (class "Default")
      (node (ref "C148") (pin "2") (pinfunction "2_2") (pintype "passive"))
      (node (ref "C151") (pin "2") (pinfunction "2_2") (pintype "passive"))
      (node (ref "R99") (pin "1") (pinfunction "1_1") (pintype "passive"))
      (node (ref "U9") (pin "1") (pinfunction "IN_1") (pintype "passive"))
    )
    (net (code "43") (name "Net-(U9-OUT)") (class "Default")
      (node (ref "C149") (pin "2") (pinfunction "2_2") (pintype "passive"))
      (node (ref "C150") (pin "2") (pinfunction "2_2") (pintype "passive"))
      (node (ref "R100") (pin "2") (pinfunction "2_2") (pintype "passive"))
      (node (ref "U9") (pin "3") (pinfunction "OUT_3") (pintype "passive"))
    )
    (net (code "44") (name "Net-(U10-EN)") (class "Default")
      (node (ref "R115") (pin "2") (pinfunction "2_2") (pintype "passive"))
      (node (ref "R117") (pin "2") (pinfunction "2_2") (pintype "passive"))
      (node (ref "U10") (pin "3") (pinfunction "EN_3") (pintype "passive"))
    )
    (net (code "45") (name "Net-(U10-FB)") (class "Default")
      (node (ref "C163") (pin "1") (pinfunction "1_1") (pintype "passive"))
      (node (ref "C164") (pin "1") (pinfunction "1_1") (pintype "passive"))
      (node (ref "R116") (pin "2") (pinfunction "2_2") (pintype "passive"))
      (node (ref "R120") (pin "2") (pinfunction "2_2") (pintype "passive"))
      (node (ref "U10") (pin "6") (pinfunction "FB_6") (pintype "passive"))
    )
    (net (code "46") (name "Net-(U10-RON)") (class "Default")
      (node (ref "R108") (pin "1") (pinfunction "1_1") (pintype "passive"))
      (node (ref "U10") (pin "2") (pinfunction "RON_2") (pintype "passive"))
    )
    (net (code "47") (name "Net-(U10-SS)") (class "Default")
      (node (ref "C170") (pin "1") (pinfunction "1_1") (pintype "passive"))
      (node (ref "C171") (pin "1") (pinfunction "1_1") (pintype "passive"))
      (node (ref "U10") (pin "5") (pinfunction "SS_5") (pintype "passive"))
    )
    (net (code "48") (name "Net-(U10-VIN)") (class "Default")
      (node (ref "C161") (pin "2") (pinfunction "2_2") (pintype "passive"))
      (node (ref "C162") (pin "2") (pinfunction "2_2") (pintype "passive"))
      (node (ref "L19") (pin "2") (pinfunction "2_2") (pintype "passive"))
      (node (ref "R108") (pin "2") (pinfunction "2_2") (pintype "passive"))
      (node (ref "R115") (pin "1") (pinfunction "1_1") (pintype "passive"))
      (node (ref "U10") (pin "1") (pinfunction "VIN_1") (pintype "passive"))
    )
    (net (code "49") (name "Net-(U11-+Vin)") (class "Default")
      (node (ref "C172") (pin "2") (pinfunction "2_2") (pintype "passive"))
      (node (ref "L21") (pin "2") (pinfunction "2_2") (pintype "passive"))
      (node (ref "R118") (pin "1") (pinfunction "1_1") (pintype "passive"))
      (node (ref "U11") (pin "6") (pinfunction "+Vin_6") (pintype "passive"))
    )
    (net (code "50") (name "Net-(U11-GND1)") (class "Default")
      (node (ref "R110") (pin "1") (pinfunction "1_1") (pintype "passive"))
      (node (ref "U11") (pin "4") (pinfunction "GND1_4") (pintype "passive"))
    )
    (net (code "51") (name "Net-(U11-HV)") (class "Default")
      (node (ref "C165") (pin "2") (pinfunction "2_2") (pintype "passive"))
      (node (ref "R112") (pin "2") (pinfunction "2_2") (pintype "passive"))
      (node (ref "U11") (pin "7") (pinfunction "HV_7") (pintype "passive"))
    )
    (net (code "52") (name "Net-(U11-R{slash}S)") (class "Default")
      (node (ref "R113") (pin "2") (pinfunction "2_2") (pintype "passive"))
      (node (ref "R118") (pin "2") (pinfunction "2_2") (pintype "passive"))
      (node (ref "U11") (pin "3") (pinfunction "R/S_3") (pintype "passive"))
    )
    (net (code "53") (name "Net-(U11-Vadj)") (class "Default")
      (node (ref "R110") (pin "2") (pinfunction "2_2") (pintype "passive"))
      (node (ref "R111") (pin "1") (pinfunction "1_1") (pintype "passive"))
      (node (ref "U11") (pin "2") (pinfunction "Vadj_2") (pintype "passive"))
    )
    (net (code "54") (name "Net-(U11-Vref)") (class "Default")
      (node (ref "R111") (pin "2") (pinfunction "2_2") (pintype "passive"))
      (node (ref "U11") (pin "1") (pinfunction "Vref_1") (pintype "passive"))
    )
    (net (code "55") (name "Net-(U12-Vin+)") (class "Default")
      (node (ref "C173") (pin "1") (pinfunction "1_1") (pintype "passive"))
      (node (ref "C174") (pin "1") (pinfunction "1_1") (pintype "passive"))
      (node (ref "C175") (pin "1") (pinfunction "1_1") (pintype "passive"))
      (node (ref "C176") (pin "1") (pinfunction "1_1") (pintype "passive"))
      (node (ref "D11") (pin "1") (pinfunction "1_1") (pintype "passive"))
      (node (ref "D12") (pin "1") (pinfunction "1_1") (pintype "passive"))
      (node (ref "L22") (pin "1") (pinfunction "1_1") (pintype "passive"))
      (node (ref "L22") (pin "3") (pinfunction "3_3") (pintype "passive"))
      (node (ref "R121") (pin "2") (pinfunction "2_2") (pintype "passive"))
      (node (ref "R122") (pin "2") (pinfunction "2_2") (pintype "passive"))
      (node (ref "R123") (pin "2") (pinfunction "2_2") (pintype "passive"))
      (node (ref "U12") (pin "3") (pinfunction "Vin+_3") (pintype "passive"))
    )
    (net (code "56") (name "unconnected-(D7-Pad2)") (class "Default")
      (node (ref "D7") (pin "2") (pinfunction "2_2") (pintype "passive"))
    )
    (net (code "57") (name "unconnected-(R109-Pad1)") (class "Default")
      (node (ref "R109") (pin "1") (pinfunction "1_1") (pintype "passive"))
    )
    (net (code "58") (name "unconnected-(R112-Pad1)") (class "Default")
      (node (ref "R112") (pin "1") (pinfunction "1_1") (pintype "passive"))
    )
  )
)
